# PiGateway2.net
KiCad netlist of a schematic drawn in EAGLE
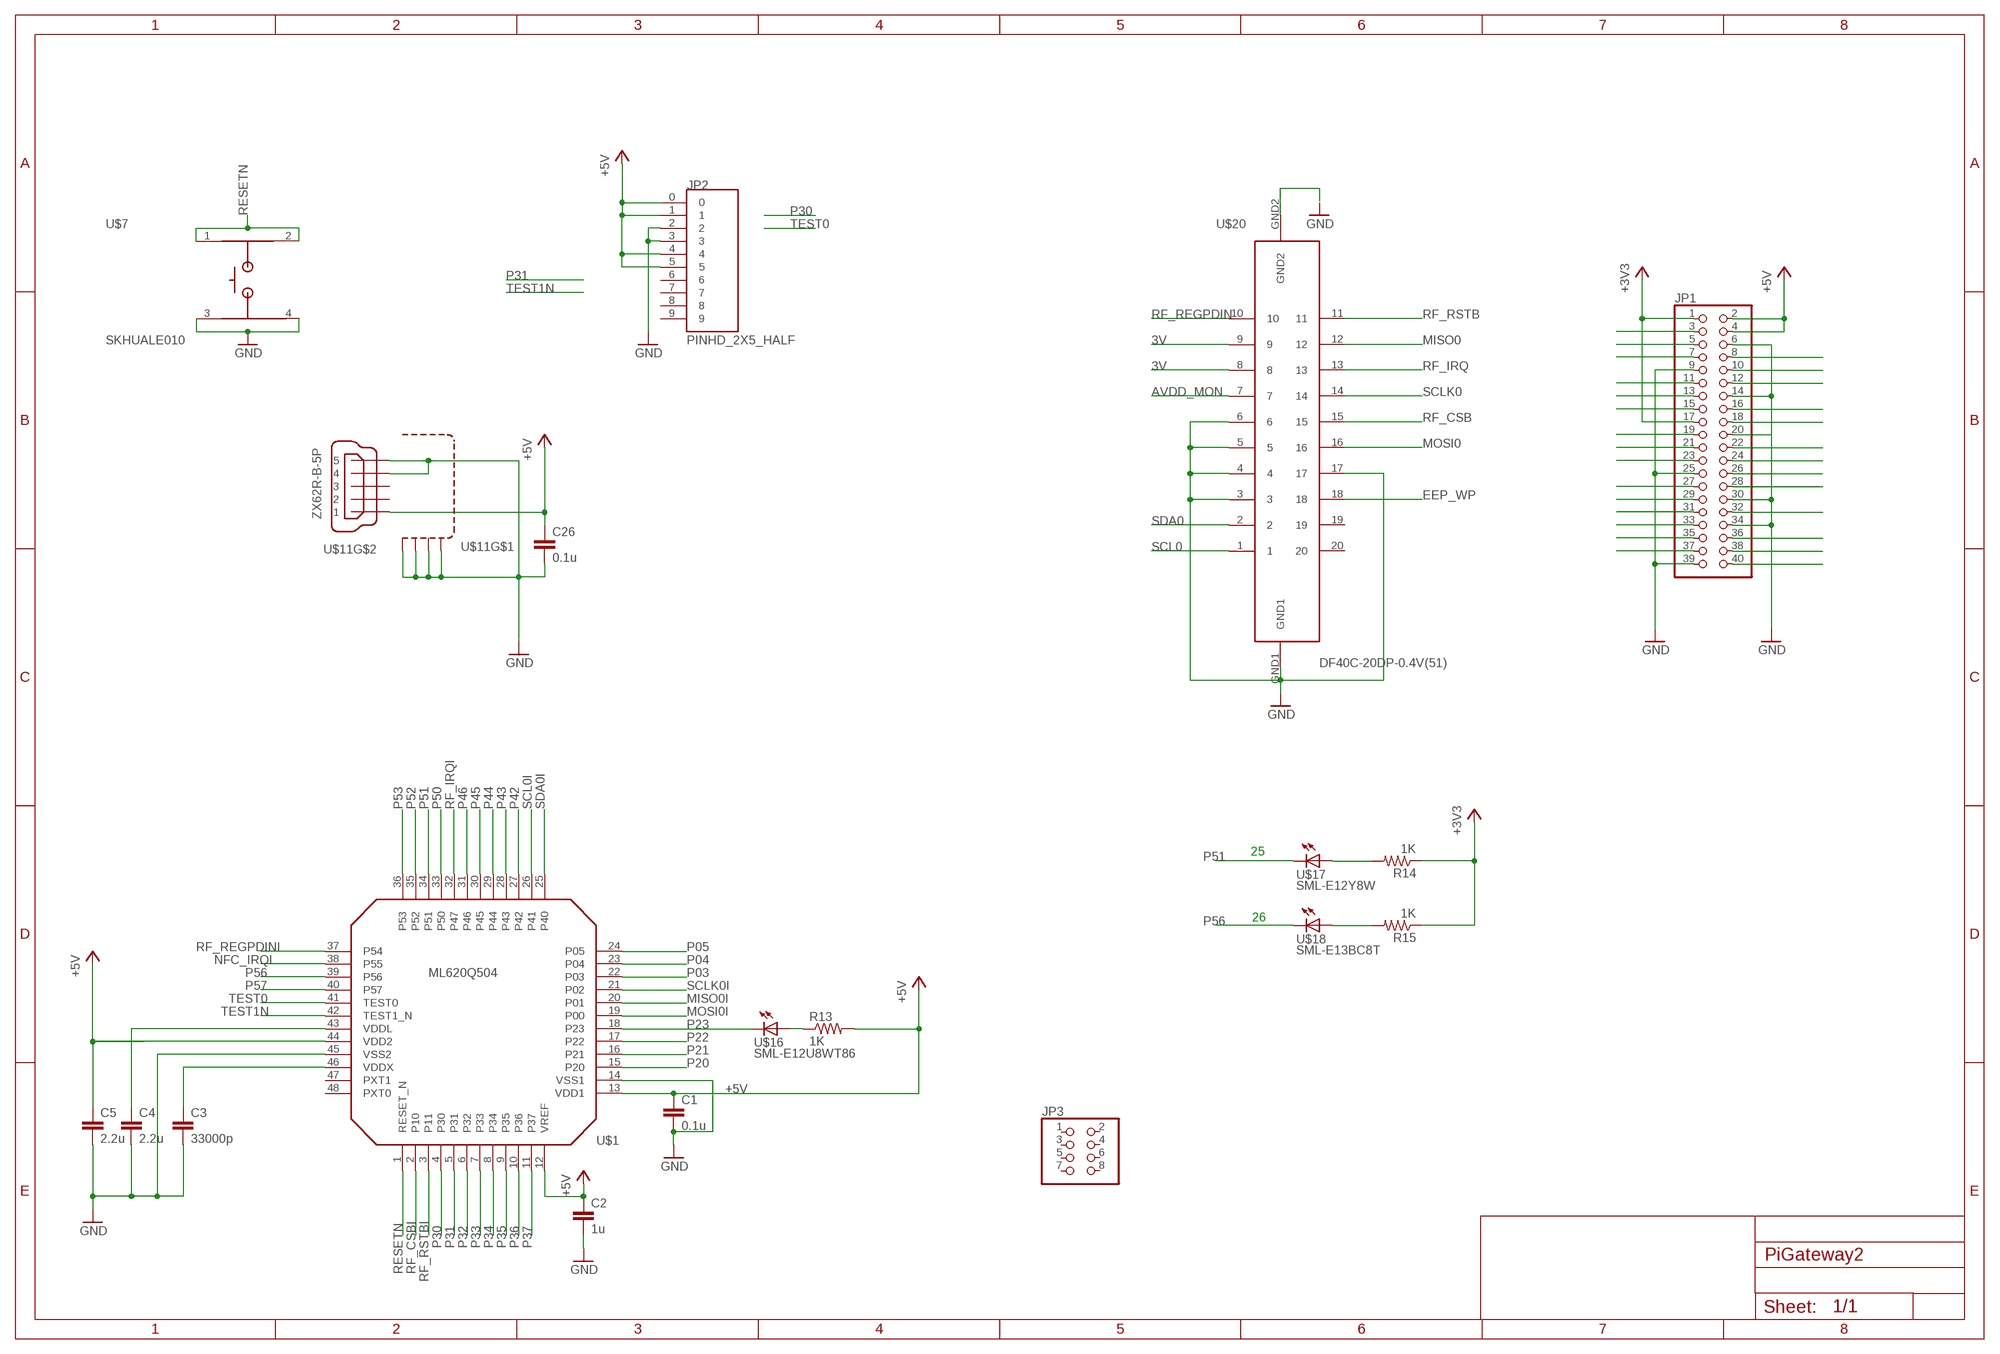
[diagram p0: schematic, sheet 1]

(export (version "E")
  (design (tool "Eeschema 10.0.6"))
  (components
    (comp (ref "C1")
      (value "0.1u")
      (footprint "eagle-import:C0402")
      (libsource (lib "eagle-import") (part "C-EUC0402"))
    )
    (comp (ref "C2")
      (value "1u")
      (footprint "eagle-import:C0402")
      (libsource (lib "eagle-import") (part "C-EUC0402"))
    )
    (comp (ref "C3")
      (value "33000p")
      (footprint "eagle-import:C0402")
      (libsource (lib "eagle-import") (part "C-EUC0402"))
    )
    (comp (ref "C4")
      (value "2.2u")
      (footprint "eagle-import:C0402")
      (libsource (lib "eagle-import") (part "C-EUC0402"))
    )
    (comp (ref "C5")
      (value "2.2u")
      (footprint "eagle-import:C0402")
      (libsource (lib "eagle-import") (part "C-EUC0402"))
    )
    (comp (ref "C26")
      (value "0.1u")
      (footprint "eagle-import:C0402")
      (libsource (lib "eagle-import") (part "C-EUC0402"))
    )
    (comp (ref "JP1")
      (value "PINHD-2X20")
      (footprint "eagle-import:2X20")
      (libsource (lib "eagle-import") (part "PINHD-2X20"))
    )
    (comp (ref "JP2")
      (value "PINHD_2X5_HALF")
      (footprint "eagle-import:PINHD_2X5_HALF")
      (libsource (lib "eagle-import") (part "PINHD_2X5_HALF"))
    )
    (comp (ref "JP3")
      (value "PINHD-2X4")
      (footprint "eagle-import:2X04")
      (libsource (lib "eagle-import") (part "PINHD-2X4"))
    )
    (comp (ref "R13")
      (value "1K")
      (footprint "eagle-import:R0402")
      (libsource (lib "eagle-import") (part "R-US_R0402"))
    )
    (comp (ref "R14")
      (value "1K")
      (footprint "eagle-import:R0402")
      (libsource (lib "eagle-import") (part "R-US_R0402"))
    )
    (comp (ref "R15")
      (value "1K")
      (footprint "eagle-import:R0402")
      (libsource (lib "eagle-import") (part "R-US_R0402"))
    )
    (comp (ref "U$1")
      (value "ML620Q504")
      (footprint "eagle-import:ML620Q504")
      (libsource (lib "eagle-import") (part "ML620Q504"))
    )
    (comp (ref "U$7")
      (value "SKHUALE010")
      (footprint "eagle-import:SKHUALE010")
      (libsource (lib "eagle-import") (part "SKHUALE010"))
    )
    (comp (ref "U$11")
      (value "ZX62R-B-5P")
      (footprint "eagle-import:ZX62R-B-5P")
      (libsource (lib "eagle-import") (part "MICRO-USB-SHIELD-ZX62R-B-5P"))
    )
    (comp (ref "U$16")
      (value "SML-E12U8WT86")
      (footprint "eagle-import:SML-E1X")
      (libsource (lib "eagle-import") (part "SML-E1X"))
    )
    (comp (ref "U$17")
      (value "SML-E12Y8W")
      (footprint "eagle-import:SML-E1X")
      (libsource (lib "eagle-import") (part "SML-E1X"))
    )
    (comp (ref "U$18")
      (value "SML-E13BC8T")
      (footprint "eagle-import:SML-E1X")
      (libsource (lib "eagle-import") (part "SML-E1X"))
    )
    (comp (ref "U$20")
      (value "DF40C-20DP-0.4V(51)")
      (footprint "eagle-import:BP3596A")
      (libsource (lib "eagle-import") (part "BP3596A"))
    )
  )
  (nets
    (net (code "1") (name "+3V3") (class "Default")
      (node (ref "JP1") (pin "1") (pinfunction "1_1") (pintype "passive"))
      (node (ref "JP1") (pin "17") (pinfunction "17_17") (pintype "passive"))
      (node (ref "R14") (pin "1") (pinfunction "1_1") (pintype "passive"))
      (node (ref "R15") (pin "1") (pinfunction "1_1") (pintype "passive"))
    )
    (net (code "2") (name "+5V") (class "Default")
      (node (ref "C1") (pin "1") (pinfunction "1_1") (pintype "passive"))
      (node (ref "C2") (pin "1") (pinfunction "1_1") (pintype "passive"))
      (node (ref "C26") (pin "1") (pinfunction "1_1") (pintype "passive"))
      (node (ref "C5") (pin "1") (pinfunction "1_1") (pintype "passive"))
      (node (ref "JP1") (pin "2") (pinfunction "2_2") (pintype "passive"))
      (node (ref "JP1") (pin "4") (pinfunction "4_4") (pintype "passive"))
      (node (ref "JP2") (pin "0") (pinfunction "0_0") (pintype "bidirectional"))
      (node (ref "JP2") (pin "1") (pinfunction "1_1") (pintype "bidirectional"))
      (node (ref "JP2") (pin "4") (pinfunction "4_4") (pintype "bidirectional"))
      (node (ref "JP2") (pin "5") (pinfunction "5_5") (pintype "bidirectional"))
      (node (ref "R13") (pin "2") (pinfunction "2_2") (pintype "passive"))
      (node (ref "U$1") (pin "12") (pinfunction "VREF_12") (pintype "bidirectional"))
      (node (ref "U$1") (pin "13") (pinfunction "VDD1_13") (pintype "bidirectional"))
      (node (ref "U$1") (pin "44") (pinfunction "VDD2_44") (pintype "bidirectional"))
      (node (ref "U$11") (pin "1") (pinfunction "1_1") (pintype "input"))
    )
    (net (code "3") (name "/3V") (class "Default")
      (node (ref "U$20") (pin "8") (pinfunction "8_8") (pintype "bidirectional"))
      (node (ref "U$20") (pin "9") (pinfunction "9_9") (pintype "bidirectional"))
    )
    (net (code "4") (name "/AVDD_MON") (class "Default")
      (node (ref "U$20") (pin "7") (pinfunction "7_7") (pintype "bidirectional"))
    )
    (net (code "5") (name "/EEP_WP") (class "Default")
      (node (ref "U$20") (pin "18") (pinfunction "18_18") (pintype "bidirectional"))
    )
    (net (code "6") (name "/MISO0") (class "Default")
      (node (ref "U$20") (pin "12") (pinfunction "12_12") (pintype "bidirectional"))
    )
    (net (code "7") (name "/MISO0I") (class "Default")
      (node (ref "U$1") (pin "20") (pinfunction "P01_20") (pintype "bidirectional"))
    )
    (net (code "8") (name "/MOSI0") (class "Default")
      (node (ref "U$20") (pin "16") (pinfunction "16_16") (pintype "bidirectional"))
    )
    (net (code "9") (name "/MOSI0I") (class "Default")
      (node (ref "U$1") (pin "19") (pinfunction "P00_19") (pintype "bidirectional"))
    )
    (net (code "10") (name "/NFC_IRQI") (class "Default")
      (node (ref "U$1") (pin "38") (pinfunction "P55_38") (pintype "bidirectional"))
    )
    (net (code "11") (name "/P03") (class "Default")
      (node (ref "U$1") (pin "22") (pinfunction "P03_22") (pintype "bidirectional"))
    )
    (net (code "12") (name "/P04") (class "Default")
      (node (ref "U$1") (pin "23") (pinfunction "P04_23") (pintype "bidirectional"))
    )
    (net (code "13") (name "/P05") (class "Default")
      (node (ref "U$1") (pin "24") (pinfunction "P05_24") (pintype "bidirectional"))
    )
    (net (code "14") (name "/P20") (class "Default")
      (node (ref "U$1") (pin "15") (pinfunction "P20_15") (pintype "bidirectional"))
    )
    (net (code "15") (name "/P21") (class "Default")
      (node (ref "U$1") (pin "16") (pinfunction "P21_16") (pintype "bidirectional"))
    )
    (net (code "16") (name "/P22") (class "Default")
      (node (ref "U$1") (pin "17") (pinfunction "P22_17") (pintype "bidirectional"))
    )
    (net (code "17") (name "/P23") (class "Default")
      (node (ref "U$1") (pin "18") (pinfunction "P23_18") (pintype "bidirectional"))
      (node (ref "U$16") (pin "C") (pinfunction "C_C") (pintype "passive"))
    )
    (net (code "18") (name "/P30") (class "Default")
      (node (ref "U$1") (pin "4") (pinfunction "P30_4") (pintype "bidirectional"))
    )
    (net (code "19") (name "/P31") (class "Default")
      (node (ref "U$1") (pin "5") (pinfunction "P31_5") (pintype "bidirectional"))
    )
    (net (code "20") (name "/P32") (class "Default")
      (node (ref "U$1") (pin "6") (pinfunction "P32_6") (pintype "bidirectional"))
    )
    (net (code "21") (name "/P33") (class "Default")
      (node (ref "U$1") (pin "7") (pinfunction "P33_7") (pintype "bidirectional"))
    )
    (net (code "22") (name "/P34") (class "Default")
      (node (ref "U$1") (pin "8") (pinfunction "P34_8") (pintype "bidirectional"))
    )
    (net (code "23") (name "/P35") (class "Default")
      (node (ref "U$1") (pin "9") (pinfunction "P35_9") (pintype "bidirectional"))
    )
    (net (code "24") (name "/P36") (class "Default")
      (node (ref "U$1") (pin "10") (pinfunction "P36_10") (pintype "bidirectional"))
    )
    (net (code "25") (name "/P37") (class "Default")
      (node (ref "U$1") (pin "11") (pinfunction "P37_11") (pintype "bidirectional"))
    )
    (net (code "26") (name "/P42") (class "Default")
      (node (ref "U$1") (pin "27") (pinfunction "P42_27") (pintype "bidirectional"))
    )
    (net (code "27") (name "/P43") (class "Default")
      (node (ref "U$1") (pin "28") (pinfunction "P43_28") (pintype "bidirectional"))
    )
    (net (code "28") (name "/P44") (class "Default")
      (node (ref "U$1") (pin "29") (pinfunction "P44_29") (pintype "bidirectional"))
    )
    (net (code "29") (name "/P45") (class "Default")
      (node (ref "U$1") (pin "30") (pinfunction "P45_30") (pintype "bidirectional"))
    )
    (net (code "30") (name "/P46") (class "Default")
      (node (ref "U$1") (pin "31") (pinfunction "P46_31") (pintype "bidirectional"))
    )
    (net (code "31") (name "/P50") (class "Default")
      (node (ref "U$1") (pin "33") (pinfunction "P50_33") (pintype "bidirectional"))
    )
    (net (code "32") (name "/P51") (class "Default")
      (node (ref "U$1") (pin "34") (pinfunction "P51_34") (pintype "bidirectional"))
      (node (ref "U$17") (pin "C") (pinfunction "C_C") (pintype "passive"))
    )
    (net (code "33") (name "/P52") (class "Default")
      (node (ref "U$1") (pin "35") (pinfunction "P52_35") (pintype "bidirectional"))
    )
    (net (code "34") (name "/P53") (class "Default")
      (node (ref "U$1") (pin "36") (pinfunction "P53_36") (pintype "bidirectional"))
    )
    (net (code "35") (name "/P56") (class "Default")
      (node (ref "U$1") (pin "39") (pinfunction "P56_39") (pintype "bidirectional"))
      (node (ref "U$18") (pin "C") (pinfunction "C_C") (pintype "passive"))
    )
    (net (code "36") (name "/P57") (class "Default")
      (node (ref "U$1") (pin "40") (pinfunction "P57_40") (pintype "bidirectional"))
    )
    (net (code "37") (name "/RESETN") (class "Default")
      (node (ref "U$1") (pin "1") (pinfunction "RESET_N_1") (pintype "bidirectional"))
      (node (ref "U$7") (pin "1") (pinfunction "1_1") (pintype "bidirectional"))
      (node (ref "U$7") (pin "2") (pinfunction "2_2") (pintype "bidirectional"))
    )
    (net (code "38") (name "/RF_CSB") (class "Default")
      (node (ref "U$20") (pin "15") (pinfunction "15_15") (pintype "bidirectional"))
    )
    (net (code "39") (name "/RF_CSBI") (class "Default")
      (node (ref "U$1") (pin "2") (pinfunction "P10_2") (pintype "bidirectional"))
    )
    (net (code "40") (name "/RF_IRQ") (class "Default")
      (node (ref "U$20") (pin "13") (pinfunction "13_13") (pintype "bidirectional"))
    )
    (net (code "41") (name "/RF_IRQI") (class "Default")
      (node (ref "U$1") (pin "32") (pinfunction "P47_32") (pintype "bidirectional"))
    )
    (net (code "42") (name "/RF_REGPDIN") (class "Default")
      (node (ref "U$20") (pin "10") (pinfunction "10_10") (pintype "bidirectional"))
    )
    (net (code "43") (name "/RF_REGPDINI") (class "Default")
      (node (ref "U$1") (pin "37") (pinfunction "P54_37") (pintype "bidirectional"))
    )
    (net (code "44") (name "/RF_RSTB") (class "Default")
      (node (ref "U$20") (pin "11") (pinfunction "11_11") (pintype "bidirectional"))
    )
    (net (code "45") (name "/RF_RSTBI") (class "Default")
      (node (ref "U$1") (pin "3") (pinfunction "P11_3") (pintype "bidirectional"))
    )
    (net (code "46") (name "/SCL0") (class "Default")
      (node (ref "U$20") (pin "1") (pinfunction "1_1") (pintype "bidirectional"))
    )
    (net (code "47") (name "/SCL0I") (class "Default")
      (node (ref "U$1") (pin "26") (pinfunction "P41_26") (pintype "bidirectional"))
    )
    (net (code "48") (name "/SCLK0") (class "Default")
      (node (ref "U$20") (pin "14") (pinfunction "14_14") (pintype "bidirectional"))
    )
    (net (code "49") (name "/SCLK0I") (class "Default")
      (node (ref "U$1") (pin "21") (pinfunction "P02_21") (pintype "bidirectional"))
    )
    (net (code "50") (name "/SDA0") (class "Default")
      (node (ref "U$20") (pin "2") (pinfunction "2_2") (pintype "bidirectional"))
    )
    (net (code "51") (name "/SDA0I") (class "Default")
      (node (ref "U$1") (pin "25") (pinfunction "P40_25") (pintype "bidirectional"))
    )
    (net (code "52") (name "/TEST0") (class "Default")
      (node (ref "U$1") (pin "41") (pinfunction "TEST0_41") (pintype "bidirectional"))
    )
    (net (code "53") (name "/TEST1N") (class "Default")
      (node (ref "U$1") (pin "42") (pinfunction "TEST1_N_42") (pintype "bidirectional"))
    )
    (net (code "54") (name "GND") (class "Default")
      (node (ref "C1") (pin "2") (pinfunction "2_2") (pintype "passive"))
      (node (ref "C2") (pin "2") (pinfunction "2_2") (pintype "passive"))
      (node (ref "C26") (pin "2") (pinfunction "2_2") (pintype "passive"))
      (node (ref "C3") (pin "2") (pinfunction "2_2") (pintype "passive"))
      (node (ref "C4") (pin "2") (pinfunction "2_2") (pintype "passive"))
      (node (ref "C5") (pin "2") (pinfunction "2_2") (pintype "passive"))
      (node (ref "JP1") (pin "14") (pinfunction "14_14") (pintype "passive"))
      (node (ref "JP1") (pin "20") (pinfunction "20_20") (pintype "passive"))
      (node (ref "JP1") (pin "25") (pinfunction "25_25") (pintype "passive"))
      (node (ref "JP1") (pin "30") (pinfunction "30_30") (pintype "passive"))
      (node (ref "JP1") (pin "34") (pinfunction "34_34") (pintype "passive"))
      (node (ref "JP1") (pin "39") (pinfunction "39_39") (pintype "passive"))
      (node (ref "JP1") (pin "6") (pinfunction "6_6") (pintype "passive"))
      (node (ref "JP1") (pin "9") (pinfunction "9_9") (pintype "passive"))
      (node (ref "JP2") (pin "2") (pinfunction "2_2") (pintype "bidirectional"))
      (node (ref "JP2") (pin "3") (pinfunction "3_3") (pintype "bidirectional"))
      (node (ref "U$1") (pin "14") (pinfunction "VSS1_14") (pintype "bidirectional"))
      (node (ref "U$1") (pin "45") (pinfunction "VSS2_45") (pintype "bidirectional"))
      (node (ref "U$11") (pin "4") (pinfunction "4_4") (pintype "input"))
      (node (ref "U$11") (pin "5") (pinfunction "5_5") (pintype "input"))
      (node (ref "U$11") (pin "M1") (pinfunction "S1_M1") (pintype "passive"))
      (node (ref "U$11") (pin "M2") (pinfunction "S2_M2") (pintype "passive"))
      (node (ref "U$11") (pin "M3") (pinfunction "S3_M3") (pintype "passive"))
      (node (ref "U$11") (pin "M4") (pinfunction "S4_M4") (pintype "passive"))
      (node (ref "U$20") (pin "17") (pinfunction "17_17") (pintype "bidirectional"))
      (node (ref "U$20") (pin "3") (pinfunction "3_3") (pintype "bidirectional"))
      (node (ref "U$20") (pin "4") (pinfunction "4_4") (pintype "bidirectional"))
      (node (ref "U$20") (pin "5") (pinfunction "5_5") (pintype "bidirectional"))
      (node (ref "U$20") (pin "6") (pinfunction "6_6") (pintype "bidirectional"))
      (node (ref "U$20") (pin "GND1") (pinfunction "GND1_GND1") (pintype "bidirectional"))
      (node (ref "U$7") (pin "3") (pinfunction "3_3") (pintype "bidirectional"))
      (node (ref "U$7") (pin "4") (pinfunction "4_4") (pintype "bidirectional"))
    )
    (net (code "55") (name "Net-(R13-Pad1)") (class "Default")
      (node (ref "R13") (pin "1") (pinfunction "1_1") (pintype "passive"))
      (node (ref "U$16") (pin "A") (pinfunction "A_A") (pintype "passive"))
    )
    (net (code "56") (name "Net-(R14-Pad2)") (class "Default")
      (node (ref "R14") (pin "2") (pinfunction "2_2") (pintype "passive"))
      (node (ref "U$17") (pin "A") (pinfunction "A_A") (pintype "passive"))
    )
    (net (code "57") (name "Net-(R15-Pad2)") (class "Default")
      (node (ref "R15") (pin "2") (pinfunction "2_2") (pintype "passive"))
      (node (ref "U$18") (pin "A") (pinfunction "A_A") (pintype "passive"))
    )
    (net (code "58") (name "Net-(U$1-VDDL)") (class "Default")
      (node (ref "C4") (pin "1") (pinfunction "1_1") (pintype "passive"))
      (node (ref "U$1") (pin "43") (pinfunction "VDDL_43") (pintype "bidirectional"))
    )
    (net (code "59") (name "Net-(U$1-VDDX)") (class "Default")
      (node (ref "C3") (pin "1") (pinfunction "1_1") (pintype "passive"))
      (node (ref "U$1") (pin "46") (pinfunction "VDDX_46") (pintype "bidirectional"))
    )
    (net (code "60") (name "unconnected-(JP1-Pad3)") (class "Default")
      (node (ref "JP1") (pin "3") (pinfunction "3_3") (pintype "passive"))
    )
    (net (code "61") (name "unconnected-(JP1-Pad5)") (class "Default")
      (node (ref "JP1") (pin "5") (pinfunction "5_5") (pintype "passive"))
    )
    (net (code "62") (name "unconnected-(JP1-Pad7)") (class "Default")
      (node (ref "JP1") (pin "7") (pinfunction "7_7") (pintype "passive"))
    )
    (net (code "63") (name "unconnected-(JP1-Pad8)") (class "Default")
      (node (ref "JP1") (pin "8") (pinfunction "8_8") (pintype "passive"))
    )
    (net (code "64") (name "unconnected-(JP1-Pad10)") (class "Default")
      (node (ref "JP1") (pin "10") (pinfunction "10_10") (pintype "passive"))
    )
    (net (code "65") (name "unconnected-(JP1-Pad11)") (class "Default")
      (node (ref "JP1") (pin "11") (pinfunction "11_11") (pintype "passive"))
    )
    (net (code "66") (name "unconnected-(JP1-Pad12)") (class "Default")
      (node (ref "JP1") (pin "12") (pinfunction "12_12") (pintype "passive"))
    )
    (net (code "67") (name "unconnected-(JP1-Pad13)") (class "Default")
      (node (ref "JP1") (pin "13") (pinfunction "13_13") (pintype "passive"))
    )
    (net (code "68") (name "unconnected-(JP1-Pad15)") (class "Default")
      (node (ref "JP1") (pin "15") (pinfunction "15_15") (pintype "passive"))
    )
    (net (code "69") (name "unconnected-(JP1-Pad16)") (class "Default")
      (node (ref "JP1") (pin "16") (pinfunction "16_16") (pintype "passive"))
    )
    (net (code "70") (name "unconnected-(JP1-Pad18)") (class "Default")
      (node (ref "JP1") (pin "18") (pinfunction "18_18") (pintype "passive"))
    )
    (net (code "71") (name "unconnected-(JP1-Pad19)") (class "Default")
      (node (ref "JP1") (pin "19") (pinfunction "19_19") (pintype "passive"))
    )
    (net (code "72") (name "unconnected-(JP1-Pad21)") (class "Default")
      (node (ref "JP1") (pin "21") (pinfunction "21_21") (pintype "passive"))
    )
    (net (code "73") (name "unconnected-(JP1-Pad22)") (class "Default")
      (node (ref "JP1") (pin "22") (pinfunction "22_22") (pintype "passive"))
    )
    (net (code "74") (name "unconnected-(JP1-Pad23)") (class "Default")
      (node (ref "JP1") (pin "23") (pinfunction "23_23") (pintype "passive"))
    )
    (net (code "75") (name "unconnected-(JP1-Pad24)") (class "Default")
      (node (ref "JP1") (pin "24") (pinfunction "24_24") (pintype "passive"))
    )
    (net (code "76") (name "unconnected-(JP1-Pad26)") (class "Default")
      (node (ref "JP1") (pin "26") (pinfunction "26_26") (pintype "passive"))
    )
    (net (code "77") (name "unconnected-(JP1-Pad27)") (class "Default")
      (node (ref "JP1") (pin "27") (pinfunction "27_27") (pintype "passive"))
    )
    (net (code "78") (name "unconnected-(JP1-Pad28)") (class "Default")
      (node (ref "JP1") (pin "28") (pinfunction "28_28") (pintype "passive"))
    )
    (net (code "79") (name "unconnected-(JP1-Pad29)") (class "Default")
      (node (ref "JP1") (pin "29") (pinfunction "29_29") (pintype "passive"))
    )
    (net (code "80") (name "unconnected-(JP1-Pad31)") (class "Default")
      (node (ref "JP1") (pin "31") (pinfunction "31_31") (pintype "passive"))
    )
    (net (code "81") (name "unconnected-(JP1-Pad32)") (class "Default")
      (node (ref "JP1") (pin "32") (pinfunction "32_32") (pintype "passive"))
    )
    (net (code "82") (name "unconnected-(JP1-Pad33)") (class "Default")
      (node (ref "JP1") (pin "33") (pinfunction "33_33") (pintype "passive"))
    )
    (net (code "83") (name "unconnected-(JP1-Pad35)") (class "Default")
      (node (ref "JP1") (pin "35") (pinfunction "35_35") (pintype "passive"))
    )
    (net (code "84") (name "unconnected-(JP1-Pad36)") (class "Default")
      (node (ref "JP1") (pin "36") (pinfunction "36_36") (pintype "passive"))
    )
    (net (code "85") (name "unconnected-(JP1-Pad37)") (class "Default")
      (node (ref "JP1") (pin "37") (pinfunction "37_37") (pintype "passive"))
    )
    (net (code "86") (name "unconnected-(JP1-Pad38)") (class "Default")
      (node (ref "JP1") (pin "38") (pinfunction "38_38") (pintype "passive"))
    )
    (net (code "87") (name "unconnected-(JP1-Pad40)") (class "Default")
      (node (ref "JP1") (pin "40") (pinfunction "40_40") (pintype "passive"))
    )
    (net (code "88") (name "unconnected-(JP2-Pad6)") (class "Default")
      (node (ref "JP2") (pin "6") (pinfunction "6_6") (pintype "bidirectional"))
    )
    (net (code "89") (name "unconnected-(JP2-Pad7)") (class "Default")
      (node (ref "JP2") (pin "7") (pinfunction "7_7") (pintype "bidirectional"))
    )
    (net (code "90") (name "unconnected-(JP2-Pad8)") (class "Default")
      (node (ref "JP2") (pin "8") (pinfunction "8_8") (pintype "bidirectional"))
    )
    (net (code "91") (name "unconnected-(JP2-Pad9)") (class "Default")
      (node (ref "JP2") (pin "9") (pinfunction "9_9") (pintype "bidirectional"))
    )
    (net (code "92") (name "unconnected-(JP3-Pad1)") (class "Default")
      (node (ref "JP3") (pin "1") (pinfunction "1_1") (pintype "passive"))
    )
    (net (code "93") (name "unconnected-(JP3-Pad2)") (class "Default")
      (node (ref "JP3") (pin "2") (pinfunction "2_2") (pintype "passive"))
    )
    (net (code "94") (name "unconnected-(JP3-Pad3)") (class "Default")
      (node (ref "JP3") (pin "3") (pinfunction "3_3") (pintype "passive"))
    )
    (net (code "95") (name "unconnected-(JP3-Pad4)") (class "Default")
      (node (ref "JP3") (pin "4") (pinfunction "4_4") (pintype "passive"))
    )
    (net (code "96") (name "unconnected-(JP3-Pad5)") (class "Default")
      (node (ref "JP3") (pin "5") (pinfunction "5_5") (pintype "passive"))
    )
    (net (code "97") (name "unconnected-(JP3-Pad6)") (class "Default")
      (node (ref "JP3") (pin "6") (pinfunction "6_6") (pintype "passive"))
    )
    (net (code "98") (name "unconnected-(JP3-Pad7)") (class "Default")
      (node (ref "JP3") (pin "7") (pinfunction "7_7") (pintype "passive"))
    )
    (net (code "99") (name "unconnected-(JP3-Pad8)") (class "Default")
      (node (ref "JP3") (pin "8") (pinfunction "8_8") (pintype "passive"))
    )
    (net (code "100") (name "unconnected-(U$1-PXT0-Pad48)") (class "Default")
      (node (ref "U$1") (pin "48") (pinfunction "PXT0_48") (pintype "bidirectional"))
    )
    (net (code "101") (name "unconnected-(U$1-PXT1-Pad47)") (class "Default")
      (node (ref "U$1") (pin "47") (pinfunction "PXT1_47") (pintype "bidirectional"))
    )
    (net (code "102") (name "unconnected-(U$11-Pad2)") (class "Default")
      (node (ref "U$11") (pin "2") (pinfunction "2_2") (pintype "input"))
    )
    (net (code "103") (name "unconnected-(U$11-Pad3)") (class "Default")
      (node (ref "U$11") (pin "3") (pinfunction "3_3") (pintype "input"))
    )
    (net (code "104") (name "unconnected-(U$20-Pad19)") (class "Default")
      (node (ref "U$20") (pin "19") (pinfunction "19_19") (pintype "bidirectional"))
    )
    (net (code "105") (name "unconnected-(U$20-Pad20)") (class "Default")
      (node (ref "U$20") (pin "20") (pinfunction "20_20") (pintype "bidirectional"))
    )
    (net (code "106") (name "unconnected-(U$20-PadGND2)") (class "Default")
      (node (ref "U$20") (pin "GND2") (pinfunction "GND2_GND2") (pintype "bidirectional"))
    )
  )
)
